# sdvx-controller-hardware.net
KiCad netlist of a schematic drawn in EAGLE
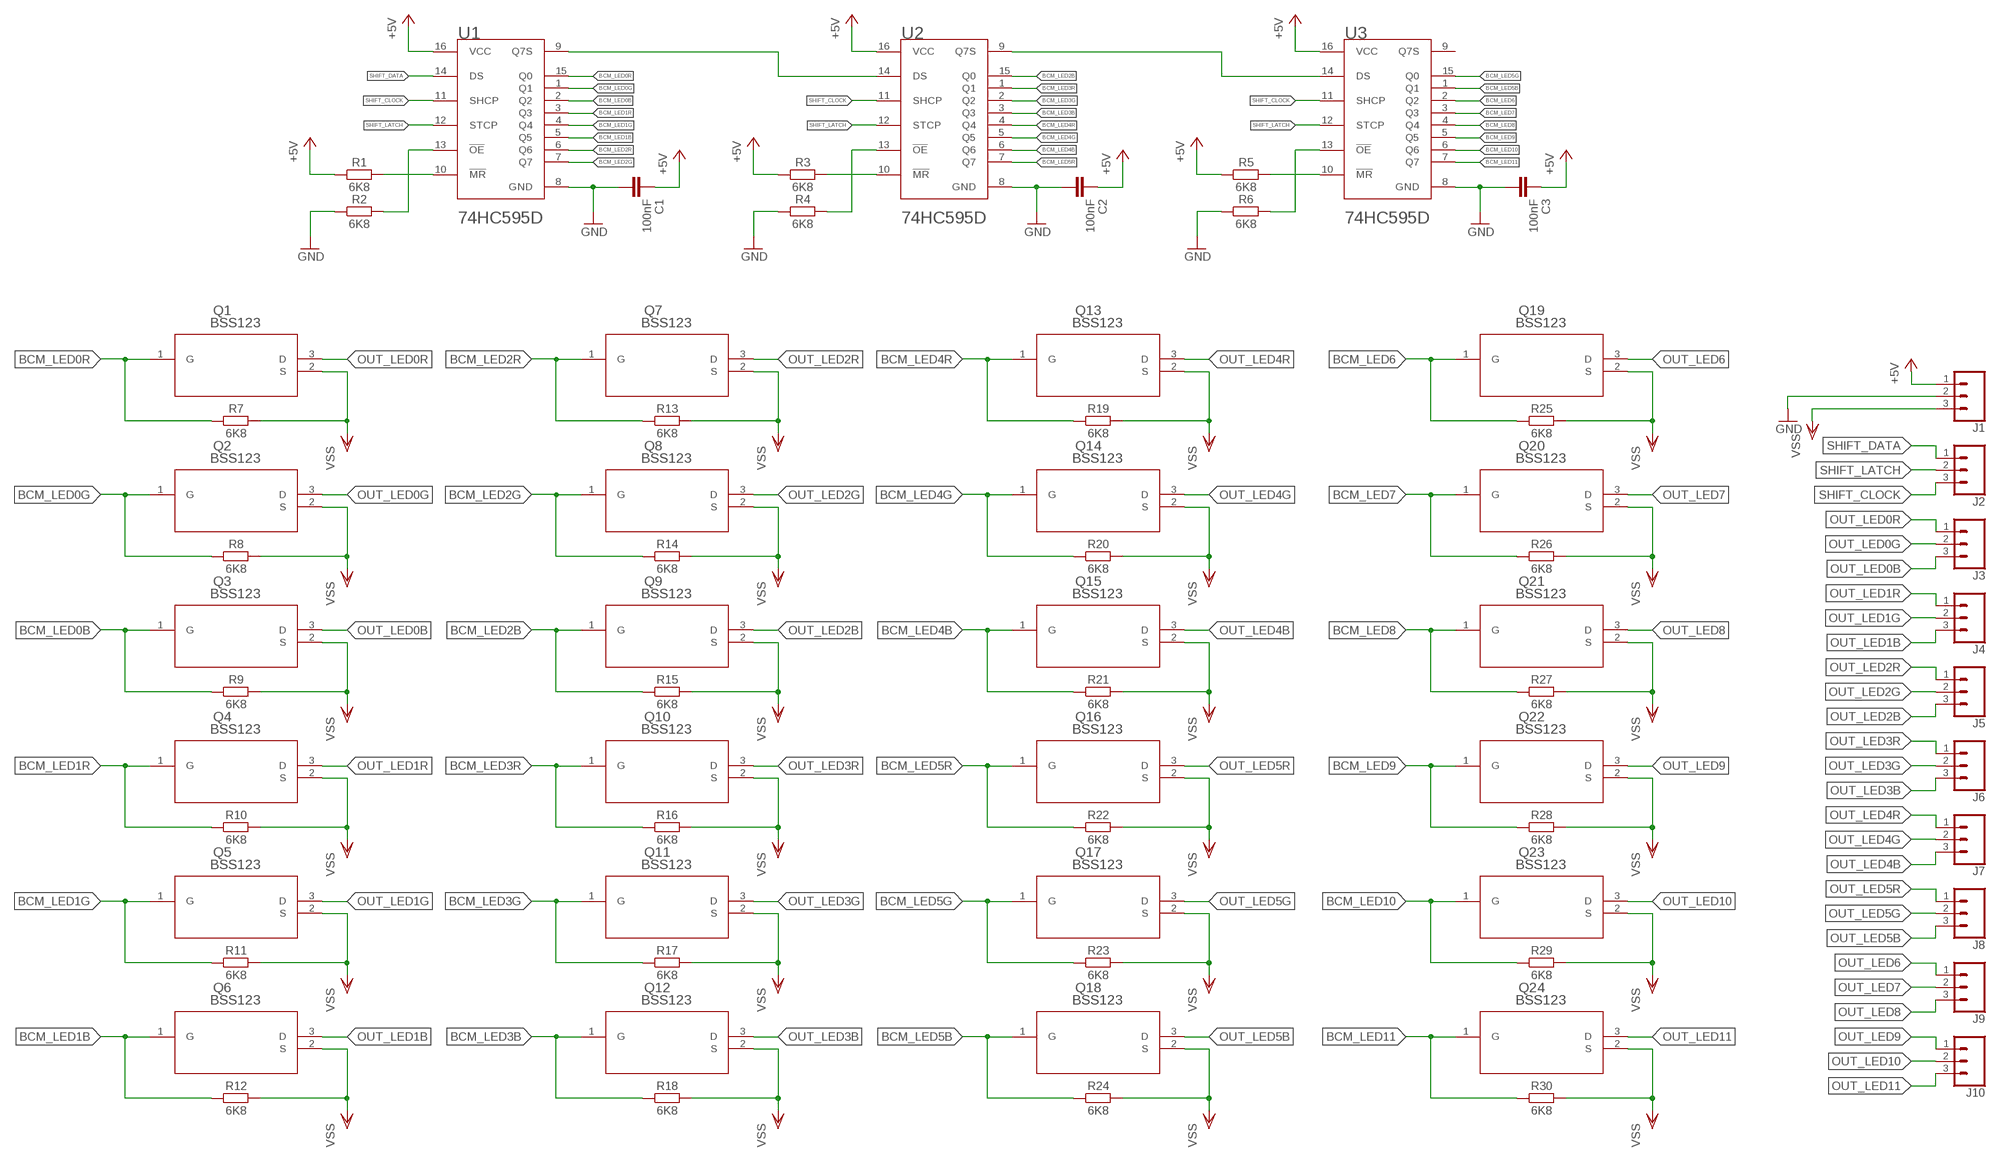
[diagram p0: schematic, sheet 1]

(export (version "E")
  (design (tool "Eeschema 10.0.6"))
  (components
    (comp (ref "C1")
      (value "100nF")
      (footprint "eagle-import:CAPC2012X110")
      (libsource (lib "eagle-import") (part "CCHIP-0805(2012-METRIC)_"))
    )
    (comp (ref "C2")
      (value "100nF")
      (footprint "eagle-import:CAPC2012X110")
      (libsource (lib "eagle-import") (part "CCHIP-0805(2012-METRIC)_"))
    )
    (comp (ref "C3")
      (value "100nF")
      (footprint "eagle-import:CAPC2012X110")
      (libsource (lib "eagle-import") (part "CCHIP-0805(2012-METRIC)_"))
    )
    (comp (ref "J1")
      (value "CONN_03-SCREW-5MM")
      (footprint "eagle-import:SCREWTERMINAL-5MM-3")
      (libsource (lib "eagle-import") (part "CONN_03-SCREW-5MM"))
    )
    (comp (ref "J2")
      (value "CONN_03-SCREW-5MM")
      (footprint "eagle-import:SCREWTERMINAL-5MM-3")
      (libsource (lib "eagle-import") (part "CONN_03-SCREW-5MM"))
    )
    (comp (ref "J3")
      (value "CONN_03-SCREW-5MM")
      (footprint "eagle-import:SCREWTERMINAL-5MM-3")
      (libsource (lib "eagle-import") (part "CONN_03-SCREW-5MM"))
    )
    (comp (ref "J4")
      (value "CONN_03-SCREW-5MM")
      (footprint "eagle-import:SCREWTERMINAL-5MM-3")
      (libsource (lib "eagle-import") (part "CONN_03-SCREW-5MM"))
    )
    (comp (ref "J5")
      (value "CONN_03-SCREW-5MM")
      (footprint "eagle-import:SCREWTERMINAL-5MM-3")
      (libsource (lib "eagle-import") (part "CONN_03-SCREW-5MM"))
    )
    (comp (ref "J6")
      (value "CONN_03-SCREW-5MM")
      (footprint "eagle-import:SCREWTERMINAL-5MM-3")
      (libsource (lib "eagle-import") (part "CONN_03-SCREW-5MM"))
    )
    (comp (ref "J7")
      (value "CONN_03-SCREW-5MM")
      (footprint "eagle-import:SCREWTERMINAL-5MM-3")
      (libsource (lib "eagle-import") (part "CONN_03-SCREW-5MM"))
    )
    (comp (ref "J8")
      (value "CONN_03-SCREW-5MM")
      (footprint "eagle-import:SCREWTERMINAL-5MM-3")
      (libsource (lib "eagle-import") (part "CONN_03-SCREW-5MM"))
    )
    (comp (ref "J9")
      (value "CONN_03-SCREW-5MM")
      (footprint "eagle-import:SCREWTERMINAL-5MM-3")
      (libsource (lib "eagle-import") (part "CONN_03-SCREW-5MM"))
    )
    (comp (ref "J10")
      (value "CONN_03-SCREW-5MM")
      (footprint "eagle-import:SCREWTERMINAL-5MM-3")
      (libsource (lib "eagle-import") (part "CONN_03-SCREW-5MM"))
    )
    (comp (ref "Q1")
      (value "BSS123")
      (footprint "eagle-import:SOT-23-3_1P4X3P040_ONS")
      (fields
        (field (name "MANUFACTURER_PART_NUMBER") "BSS123LT1")
        (field (name "COPYRIGHT") "Copyright (C) 2021 Ultra Librarian. All rights reserved.")
      )
      (libsource (lib "eagle-import") (part "BSS123LT1"))
    )
    (comp (ref "Q2")
      (value "BSS123")
      (footprint "eagle-import:SOT-23-3_1P4X3P040_ONS")
      (fields
        (field (name "MANUFACTURER_PART_NUMBER") "BSS123LT1")
        (field (name "COPYRIGHT") "Copyright (C) 2021 Ultra Librarian. All rights reserved.")
      )
      (libsource (lib "eagle-import") (part "BSS123LT1"))
    )
    (comp (ref "Q3")
      (value "BSS123")
      (footprint "eagle-import:SOT-23-3_1P4X3P040_ONS")
      (fields
        (field (name "MANUFACTURER_PART_NUMBER") "BSS123LT1")
        (field (name "COPYRIGHT") "Copyright (C) 2021 Ultra Librarian. All rights reserved.")
      )
      (libsource (lib "eagle-import") (part "BSS123LT1"))
    )
    (comp (ref "Q4")
      (value "BSS123")
      (footprint "eagle-import:SOT-23-3_1P4X3P040_ONS")
      (fields
        (field (name "MANUFACTURER_PART_NUMBER") "BSS123LT1")
        (field (name "COPYRIGHT") "Copyright (C) 2021 Ultra Librarian. All rights reserved.")
      )
      (libsource (lib "eagle-import") (part "BSS123LT1"))
    )
    (comp (ref "Q5")
      (value "BSS123")
      (footprint "eagle-import:SOT-23-3_1P4X3P040_ONS")
      (fields
        (field (name "MANUFACTURER_PART_NUMBER") "BSS123LT1")
        (field (name "COPYRIGHT") "Copyright (C) 2021 Ultra Librarian. All rights reserved.")
      )
      (libsource (lib "eagle-import") (part "BSS123LT1"))
    )
    (comp (ref "Q6")
      (value "BSS123")
      (footprint "eagle-import:SOT-23-3_1P4X3P040_ONS")
      (fields
        (field (name "MANUFACTURER_PART_NUMBER") "BSS123LT1")
        (field (name "COPYRIGHT") "Copyright (C) 2021 Ultra Librarian. All rights reserved.")
      )
      (libsource (lib "eagle-import") (part "BSS123LT1"))
    )
    (comp (ref "Q7")
      (value "BSS123")
      (footprint "eagle-import:SOT-23-3_1P4X3P040_ONS")
      (fields
        (field (name "MANUFACTURER_PART_NUMBER") "BSS123LT1")
        (field (name "COPYRIGHT") "Copyright (C) 2021 Ultra Librarian. All rights reserved.")
      )
      (libsource (lib "eagle-import") (part "BSS123LT1"))
    )
    (comp (ref "Q8")
      (value "BSS123")
      (footprint "eagle-import:SOT-23-3_1P4X3P040_ONS")
      (fields
        (field (name "MANUFACTURER_PART_NUMBER") "BSS123LT1")
        (field (name "COPYRIGHT") "Copyright (C) 2021 Ultra Librarian. All rights reserved.")
      )
      (libsource (lib "eagle-import") (part "BSS123LT1"))
    )
    (comp (ref "Q9")
      (value "BSS123")
      (footprint "eagle-import:SOT-23-3_1P4X3P040_ONS")
      (fields
        (field (name "MANUFACTURER_PART_NUMBER") "BSS123LT1")
        (field (name "COPYRIGHT") "Copyright (C) 2021 Ultra Librarian. All rights reserved.")
      )
      (libsource (lib "eagle-import") (part "BSS123LT1"))
    )
    (comp (ref "Q10")
      (value "BSS123")
      (footprint "eagle-import:SOT-23-3_1P4X3P040_ONS")
      (fields
        (field (name "MANUFACTURER_PART_NUMBER") "BSS123LT1")
        (field (name "COPYRIGHT") "Copyright (C) 2021 Ultra Librarian. All rights reserved.")
      )
      (libsource (lib "eagle-import") (part "BSS123LT1"))
    )
    (comp (ref "Q11")
      (value "BSS123")
      (footprint "eagle-import:SOT-23-3_1P4X3P040_ONS")
      (fields
        (field (name "MANUFACTURER_PART_NUMBER") "BSS123LT1")
        (field (name "COPYRIGHT") "Copyright (C) 2021 Ultra Librarian. All rights reserved.")
      )
      (libsource (lib "eagle-import") (part "BSS123LT1"))
    )
    (comp (ref "Q12")
      (value "BSS123")
      (footprint "eagle-import:SOT-23-3_1P4X3P040_ONS")
      (fields
        (field (name "MANUFACTURER_PART_NUMBER") "BSS123LT1")
        (field (name "COPYRIGHT") "Copyright (C) 2021 Ultra Librarian. All rights reserved.")
      )
      (libsource (lib "eagle-import") (part "BSS123LT1"))
    )
    (comp (ref "Q13")
      (value "BSS123")
      (footprint "eagle-import:SOT-23-3_1P4X3P040_ONS")
      (fields
        (field (name "MANUFACTURER_PART_NUMBER") "BSS123LT1")
        (field (name "COPYRIGHT") "Copyright (C) 2021 Ultra Librarian. All rights reserved.")
      )
      (libsource (lib "eagle-import") (part "BSS123LT1"))
    )
    (comp (ref "Q14")
      (value "BSS123")
      (footprint "eagle-import:SOT-23-3_1P4X3P040_ONS")
      (fields
        (field (name "MANUFACTURER_PART_NUMBER") "BSS123LT1")
        (field (name "COPYRIGHT") "Copyright (C) 2021 Ultra Librarian. All rights reserved.")
      )
      (libsource (lib "eagle-import") (part "BSS123LT1"))
    )
    (comp (ref "Q15")
      (value "BSS123")
      (footprint "eagle-import:SOT-23-3_1P4X3P040_ONS")
      (fields
        (field (name "MANUFACTURER_PART_NUMBER") "BSS123LT1")
        (field (name "COPYRIGHT") "Copyright (C) 2021 Ultra Librarian. All rights reserved.")
      )
      (libsource (lib "eagle-import") (part "BSS123LT1"))
    )
    (comp (ref "Q16")
      (value "BSS123")
      (footprint "eagle-import:SOT-23-3_1P4X3P040_ONS")
      (fields
        (field (name "MANUFACTURER_PART_NUMBER") "BSS123LT1")
        (field (name "COPYRIGHT") "Copyright (C) 2021 Ultra Librarian. All rights reserved.")
      )
      (libsource (lib "eagle-import") (part "BSS123LT1"))
    )
    (comp (ref "Q17")
      (value "BSS123")
      (footprint "eagle-import:SOT-23-3_1P4X3P040_ONS")
      (fields
        (field (name "MANUFACTURER_PART_NUMBER") "BSS123LT1")
        (field (name "COPYRIGHT") "Copyright (C) 2021 Ultra Librarian. All rights reserved.")
      )
      (libsource (lib "eagle-import") (part "BSS123LT1"))
    )
    (comp (ref "Q18")
      (value "BSS123")
      (footprint "eagle-import:SOT-23-3_1P4X3P040_ONS")
      (fields
        (field (name "MANUFACTURER_PART_NUMBER") "BSS123LT1")
        (field (name "COPYRIGHT") "Copyright (C) 2021 Ultra Librarian. All rights reserved.")
      )
      (libsource (lib "eagle-import") (part "BSS123LT1"))
    )
    (comp (ref "Q19")
      (value "BSS123")
      (footprint "eagle-import:SOT-23-3_1P4X3P040_ONS")
      (fields
        (field (name "MANUFACTURER_PART_NUMBER") "BSS123LT1")
        (field (name "COPYRIGHT") "Copyright (C) 2021 Ultra Librarian. All rights reserved.")
      )
      (libsource (lib "eagle-import") (part "BSS123LT1"))
    )
    (comp (ref "Q20")
      (value "BSS123")
      (footprint "eagle-import:SOT-23-3_1P4X3P040_ONS")
      (fields
        (field (name "MANUFACTURER_PART_NUMBER") "BSS123LT1")
        (field (name "COPYRIGHT") "Copyright (C) 2021 Ultra Librarian. All rights reserved.")
      )
      (libsource (lib "eagle-import") (part "BSS123LT1"))
    )
    (comp (ref "Q21")
      (value "BSS123")
      (footprint "eagle-import:SOT-23-3_1P4X3P040_ONS")
      (fields
        (field (name "MANUFACTURER_PART_NUMBER") "BSS123LT1")
        (field (name "COPYRIGHT") "Copyright (C) 2021 Ultra Librarian. All rights reserved.")
      )
      (libsource (lib "eagle-import") (part "BSS123LT1"))
    )
    (comp (ref "Q22")
      (value "BSS123")
      (footprint "eagle-import:SOT-23-3_1P4X3P040_ONS")
      (fields
        (field (name "MANUFACTURER_PART_NUMBER") "BSS123LT1")
        (field (name "COPYRIGHT") "Copyright (C) 2021 Ultra Librarian. All rights reserved.")
      )
      (libsource (lib "eagle-import") (part "BSS123LT1"))
    )
    (comp (ref "Q23")
      (value "BSS123")
      (footprint "eagle-import:SOT-23-3_1P4X3P040_ONS")
      (fields
        (field (name "MANUFACTURER_PART_NUMBER") "BSS123LT1")
        (field (name "COPYRIGHT") "Copyright (C) 2021 Ultra Librarian. All rights reserved.")
      )
      (libsource (lib "eagle-import") (part "BSS123LT1"))
    )
    (comp (ref "Q24")
      (value "BSS123")
      (footprint "eagle-import:SOT-23-3_1P4X3P040_ONS")
      (fields
        (field (name "MANUFACTURER_PART_NUMBER") "BSS123LT1")
        (field (name "COPYRIGHT") "Copyright (C) 2021 Ultra Librarian. All rights reserved.")
      )
      (libsource (lib "eagle-import") (part "BSS123LT1"))
    )
    (comp (ref "R1")
      (value "6K8")
      (footprint "eagle-import:RESC2012X65")
      (libsource (lib "eagle-import") (part "RCHIP-0805(2012-METRIC)_"))
    )
    (comp (ref "R2")
      (value "6K8")
      (footprint "eagle-import:RESC2012X65")
      (libsource (lib "eagle-import") (part "RCHIP-0805(2012-METRIC)_"))
    )
    (comp (ref "R3")
      (value "6K8")
      (footprint "eagle-import:RESC2012X65")
      (libsource (lib "eagle-import") (part "RCHIP-0805(2012-METRIC)_"))
    )
    (comp (ref "R4")
      (value "6K8")
      (footprint "eagle-import:RESC2012X65")
      (libsource (lib "eagle-import") (part "RCHIP-0805(2012-METRIC)_"))
    )
    (comp (ref "R5")
      (value "6K8")
      (footprint "eagle-import:RESC2012X65")
      (libsource (lib "eagle-import") (part "RCHIP-0805(2012-METRIC)_"))
    )
    (comp (ref "R6")
      (value "6K8")
      (footprint "eagle-import:RESC2012X65")
      (libsource (lib "eagle-import") (part "RCHIP-0805(2012-METRIC)_"))
    )
    (comp (ref "R7")
      (value "6K8")
      (footprint "eagle-import:RESC2012X65")
      (libsource (lib "eagle-import") (part "RCHIP-0805(2012-METRIC)_"))
    )
    (comp (ref "R8")
      (value "6K8")
      (footprint "eagle-import:RESC2012X65")
      (libsource (lib "eagle-import") (part "RCHIP-0805(2012-METRIC)_"))
    )
    (comp (ref "R9")
      (value "6K8")
      (footprint "eagle-import:RESC2012X65")
      (libsource (lib "eagle-import") (part "RCHIP-0805(2012-METRIC)_"))
    )
    (comp (ref "R10")
      (value "6K8")
      (footprint "eagle-import:RESC2012X65")
      (libsource (lib "eagle-import") (part "RCHIP-0805(2012-METRIC)_"))
    )
    (comp (ref "R11")
      (value "6K8")
      (footprint "eagle-import:RESC2012X65")
      (libsource (lib "eagle-import") (part "RCHIP-0805(2012-METRIC)_"))
    )
    (comp (ref "R12")
      (value "6K8")
      (footprint "eagle-import:RESC2012X65")
      (libsource (lib "eagle-import") (part "RCHIP-0805(2012-METRIC)_"))
    )
    (comp (ref "R13")
      (value "6K8")
      (footprint "eagle-import:RESC2012X65")
      (libsource (lib "eagle-import") (part "RCHIP-0805(2012-METRIC)_"))
    )
    (comp (ref "R14")
      (value "6K8")
      (footprint "eagle-import:RESC2012X65")
      (libsource (lib "eagle-import") (part "RCHIP-0805(2012-METRIC)_"))
    )
    (comp (ref "R15")
      (value "6K8")
      (footprint "eagle-import:RESC2012X65")
      (libsource (lib "eagle-import") (part "RCHIP-0805(2012-METRIC)_"))
    )
    (comp (ref "R16")
      (value "6K8")
      (footprint "eagle-import:RESC2012X65")
      (libsource (lib "eagle-import") (part "RCHIP-0805(2012-METRIC)_"))
    )
    (comp (ref "R17")
      (value "6K8")
      (footprint "eagle-import:RESC2012X65")
      (libsource (lib "eagle-import") (part "RCHIP-0805(2012-METRIC)_"))
    )
    (comp (ref "R18")
      (value "6K8")
      (footprint "eagle-import:RESC2012X65")
      (libsource (lib "eagle-import") (part "RCHIP-0805(2012-METRIC)_"))
    )
    (comp (ref "R19")
      (value "6K8")
      (footprint "eagle-import:RESC2012X65")
      (libsource (lib "eagle-import") (part "RCHIP-0805(2012-METRIC)_"))
    )
    (comp (ref "R20")
      (value "6K8")
      (footprint "eagle-import:RESC2012X65")
      (libsource (lib "eagle-import") (part "RCHIP-0805(2012-METRIC)_"))
    )
    (comp (ref "R21")
      (value "6K8")
      (footprint "eagle-import:RESC2012X65")
      (libsource (lib "eagle-import") (part "RCHIP-0805(2012-METRIC)_"))
    )
    (comp (ref "R22")
      (value "6K8")
      (footprint "eagle-import:RESC2012X65")
      (libsource (lib "eagle-import") (part "RCHIP-0805(2012-METRIC)_"))
    )
    (comp (ref "R23")
      (value "6K8")
      (footprint "eagle-import:RESC2012X65")
      (libsource (lib "eagle-import") (part "RCHIP-0805(2012-METRIC)_"))
    )
    (comp (ref "R24")
      (value "6K8")
      (footprint "eagle-import:RESC2012X65")
      (libsource (lib "eagle-import") (part "RCHIP-0805(2012-METRIC)_"))
    )
    (comp (ref "R25")
      (value "6K8")
      (footprint "eagle-import:RESC2012X65")
      (libsource (lib "eagle-import") (part "RCHIP-0805(2012-METRIC)_"))
    )
    (comp (ref "R26")
      (value "6K8")
      (footprint "eagle-import:RESC2012X65")
      (libsource (lib "eagle-import") (part "RCHIP-0805(2012-METRIC)_"))
    )
    (comp (ref "R27")
      (value "6K8")
      (footprint "eagle-import:RESC2012X65")
      (libsource (lib "eagle-import") (part "RCHIP-0805(2012-METRIC)_"))
    )
    (comp (ref "R28")
      (value "6K8")
      (footprint "eagle-import:RESC2012X65")
      (libsource (lib "eagle-import") (part "RCHIP-0805(2012-METRIC)_"))
    )
    (comp (ref "R29")
      (value "6K8")
      (footprint "eagle-import:RESC2012X65")
      (libsource (lib "eagle-import") (part "RCHIP-0805(2012-METRIC)_"))
    )
    (comp (ref "R30")
      (value "6K8")
      (footprint "eagle-import:RESC2012X65")
      (libsource (lib "eagle-import") (part "RCHIP-0805(2012-METRIC)_"))
    )
    (comp (ref "U1")
      (value "NEXPERIA_74HC595DNEXPERIA_74HC595D_0_0")
      (footprint "eagle-import:NEXPERIA_74HC595D_0")
      (fields
        (field (name "DIGIKEY_PART_NUMBER") "1727-2821-1-ND")
        (field (name "MF") "Nexperia")
        (field (name "MOUSER_PART_NUMBER") "771-74HC595D-T")
      )
      (libsource (lib "eagle-import") (part "NEXPERIA_74HC595DNEXPERIA_74HC595D_0_0"))
    )
    (comp (ref "U2")
      (value "NEXPERIA_74HC595DNEXPERIA_74HC595D_0_0")
      (footprint "eagle-import:NEXPERIA_74HC595D_0")
      (fields
        (field (name "DIGIKEY_PART_NUMBER") "1727-2821-1-ND")
        (field (name "MF") "Nexperia")
        (field (name "MOUSER_PART_NUMBER") "771-74HC595D-T")
      )
      (libsource (lib "eagle-import") (part "NEXPERIA_74HC595DNEXPERIA_74HC595D_0_0"))
    )
    (comp (ref "U3")
      (value "NEXPERIA_74HC595DNEXPERIA_74HC595D_0_0")
      (footprint "eagle-import:NEXPERIA_74HC595D_0")
      (fields
        (field (name "DIGIKEY_PART_NUMBER") "1727-2821-1-ND")
        (field (name "MF") "Nexperia")
        (field (name "MOUSER_PART_NUMBER") "771-74HC595D-T")
      )
      (libsource (lib "eagle-import") (part "NEXPERIA_74HC595DNEXPERIA_74HC595D_0_0"))
    )
  )
  (nets
    (net (code "1") (name "+5V") (class "Default")
      (node (ref "C1") (pin "1") (pinfunction "1_1") (pintype "passive"))
      (node (ref "C2") (pin "1") (pinfunction "1_1") (pintype "passive"))
      (node (ref "C3") (pin "1") (pinfunction "1_1") (pintype "passive"))
      (node (ref "J1") (pin "1") (pinfunction "1_1") (pintype "passive"))
      (node (ref "R1") (pin "1") (pinfunction "1_1") (pintype "passive"))
      (node (ref "R3") (pin "1") (pinfunction "1_1") (pintype "passive"))
      (node (ref "R5") (pin "1") (pinfunction "1_1") (pintype "passive"))
      (node (ref "U1") (pin "16") (pinfunction "VCC_16") (pintype "power_in"))
      (node (ref "U2") (pin "16") (pinfunction "VCC_16") (pintype "power_in"))
      (node (ref "U3") (pin "16") (pinfunction "VCC_16") (pintype "power_in"))
    )
    (net (code "2") (name "BCM_LED0B") (class "Default")
      (node (ref "Q3") (pin "1") (pinfunction "G_1") (pintype "passive"))
      (node (ref "R9") (pin "1") (pinfunction "1_1") (pintype "passive"))
      (node (ref "U1") (pin "2") (pinfunction "Q2_2") (pintype "output"))
    )
    (net (code "3") (name "BCM_LED0G") (class "Default")
      (node (ref "Q2") (pin "1") (pinfunction "G_1") (pintype "passive"))
      (node (ref "R8") (pin "1") (pinfunction "1_1") (pintype "passive"))
      (node (ref "U1") (pin "1") (pinfunction "Q1_1") (pintype "output"))
    )
    (net (code "4") (name "BCM_LED0R") (class "Default")
      (node (ref "Q1") (pin "1") (pinfunction "G_1") (pintype "passive"))
      (node (ref "R7") (pin "1") (pinfunction "1_1") (pintype "passive"))
      (node (ref "U1") (pin "15") (pinfunction "Q0_15") (pintype "output"))
    )
    (net (code "5") (name "BCM_LED1B") (class "Default")
      (node (ref "Q6") (pin "1") (pinfunction "G_1") (pintype "passive"))
      (node (ref "R12") (pin "1") (pinfunction "1_1") (pintype "passive"))
      (node (ref "U1") (pin "5") (pinfunction "Q5_5") (pintype "output"))
    )
    (net (code "6") (name "BCM_LED1G") (class "Default")
      (node (ref "Q5") (pin "1") (pinfunction "G_1") (pintype "passive"))
      (node (ref "R11") (pin "1") (pinfunction "1_1") (pintype "passive"))
      (node (ref "U1") (pin "4") (pinfunction "Q4_4") (pintype "output"))
    )
    (net (code "7") (name "BCM_LED1R") (class "Default")
      (node (ref "Q4") (pin "1") (pinfunction "G_1") (pintype "passive"))
      (node (ref "R10") (pin "1") (pinfunction "1_1") (pintype "passive"))
      (node (ref "U1") (pin "3") (pinfunction "Q3_3") (pintype "output"))
    )
    (net (code "8") (name "BCM_LED2B") (class "Default")
      (node (ref "Q9") (pin "1") (pinfunction "G_1") (pintype "passive"))
      (node (ref "R15") (pin "1") (pinfunction "1_1") (pintype "passive"))
      (node (ref "U2") (pin "15") (pinfunction "Q0_15") (pintype "output"))
    )
    (net (code "9") (name "BCM_LED2G") (class "Default")
      (node (ref "Q8") (pin "1") (pinfunction "G_1") (pintype "passive"))
      (node (ref "R14") (pin "1") (pinfunction "1_1") (pintype "passive"))
      (node (ref "U1") (pin "7") (pinfunction "Q7_7") (pintype "output"))
    )
    (net (code "10") (name "BCM_LED2R") (class "Default")
      (node (ref "Q7") (pin "1") (pinfunction "G_1") (pintype "passive"))
      (node (ref "R13") (pin "1") (pinfunction "1_1") (pintype "passive"))
      (node (ref "U1") (pin "6") (pinfunction "Q6_6") (pintype "output"))
    )
    (net (code "11") (name "BCM_LED3B") (class "Default")
      (node (ref "Q12") (pin "1") (pinfunction "G_1") (pintype "passive"))
      (node (ref "R18") (pin "1") (pinfunction "1_1") (pintype "passive"))
      (node (ref "U2") (pin "3") (pinfunction "Q3_3") (pintype "output"))
    )
    (net (code "12") (name "BCM_LED3G") (class "Default")
      (node (ref "Q11") (pin "1") (pinfunction "G_1") (pintype "passive"))
      (node (ref "R17") (pin "1") (pinfunction "1_1") (pintype "passive"))
      (node (ref "U2") (pin "2") (pinfunction "Q2_2") (pintype "output"))
    )
    (net (code "13") (name "BCM_LED3R") (class "Default")
      (node (ref "Q10") (pin "1") (pinfunction "G_1") (pintype "passive"))
      (node (ref "R16") (pin "1") (pinfunction "1_1") (pintype "passive"))
      (node (ref "U2") (pin "1") (pinfunction "Q1_1") (pintype "output"))
    )
    (net (code "14") (name "BCM_LED4B") (class "Default")
      (node (ref "Q15") (pin "1") (pinfunction "G_1") (pintype "passive"))
      (node (ref "R21") (pin "1") (pinfunction "1_1") (pintype "passive"))
      (node (ref "U2") (pin "6") (pinfunction "Q6_6") (pintype "output"))
    )
    (net (code "15") (name "BCM_LED4G") (class "Default")
      (node (ref "Q14") (pin "1") (pinfunction "G_1") (pintype "passive"))
      (node (ref "R20") (pin "1") (pinfunction "1_1") (pintype "passive"))
      (node (ref "U2") (pin "5") (pinfunction "Q5_5") (pintype "output"))
    )
    (net (code "16") (name "BCM_LED4R") (class "Default")
      (node (ref "Q13") (pin "1") (pinfunction "G_1") (pintype "passive"))
      (node (ref "R19") (pin "1") (pinfunction "1_1") (pintype "passive"))
      (node (ref "U2") (pin "4") (pinfunction "Q4_4") (pintype "output"))
    )
    (net (code "17") (name "BCM_LED5B") (class "Default")
      (node (ref "Q18") (pin "1") (pinfunction "G_1") (pintype "passive"))
      (node (ref "R24") (pin "1") (pinfunction "1_1") (pintype "passive"))
      (node (ref "U3") (pin "1") (pinfunction "Q1_1") (pintype "output"))
    )
    (net (code "18") (name "BCM_LED5G") (class "Default")
      (node (ref "Q17") (pin "1") (pinfunction "G_1") (pintype "passive"))
      (node (ref "R23") (pin "1") (pinfunction "1_1") (pintype "passive"))
      (node (ref "U3") (pin "15") (pinfunction "Q0_15") (pintype "output"))
    )
    (net (code "19") (name "BCM_LED5R") (class "Default")
      (node (ref "Q16") (pin "1") (pinfunction "G_1") (pintype "passive"))
      (node (ref "R22") (pin "1") (pinfunction "1_1") (pintype "passive"))
      (node (ref "U2") (pin "7") (pinfunction "Q7_7") (pintype "output"))
    )
    (net (code "20") (name "BCM_LED6") (class "Default")
      (node (ref "Q19") (pin "1") (pinfunction "G_1") (pintype "passive"))
      (node (ref "R25") (pin "1") (pinfunction "1_1") (pintype "passive"))
      (node (ref "U3") (pin "2") (pinfunction "Q2_2") (pintype "output"))
    )
    (net (code "21") (name "BCM_LED7") (class "Default")
      (node (ref "Q20") (pin "1") (pinfunction "G_1") (pintype "passive"))
      (node (ref "R26") (pin "1") (pinfunction "1_1") (pintype "passive"))
      (node (ref "U3") (pin "3") (pinfunction "Q3_3") (pintype "output"))
    )
    (net (code "22") (name "BCM_LED8") (class "Default")
      (node (ref "Q21") (pin "1") (pinfunction "G_1") (pintype "passive"))
      (node (ref "R27") (pin "1") (pinfunction "1_1") (pintype "passive"))
      (node (ref "U3") (pin "4") (pinfunction "Q4_4") (pintype "output"))
    )
    (net (code "23") (name "BCM_LED9") (class "Default")
      (node (ref "Q22") (pin "1") (pinfunction "G_1") (pintype "passive"))
      (node (ref "R28") (pin "1") (pinfunction "1_1") (pintype "passive"))
      (node (ref "U3") (pin "5") (pinfunction "Q5_5") (pintype "output"))
    )
    (net (code "24") (name "BCM_LED10") (class "Default")
      (node (ref "Q23") (pin "1") (pinfunction "G_1") (pintype "passive"))
      (node (ref "R29") (pin "1") (pinfunction "1_1") (pintype "passive"))
      (node (ref "U3") (pin "6") (pinfunction "Q6_6") (pintype "output"))
    )
    (net (code "25") (name "BCM_LED11") (class "Default")
      (node (ref "Q24") (pin "1") (pinfunction "G_1") (pintype "passive"))
      (node (ref "R30") (pin "1") (pinfunction "1_1") (pintype "passive"))
      (node (ref "U3") (pin "7") (pinfunction "Q7_7") (pintype "output"))
    )
    (net (code "26") (name "GND") (class "Default")
      (node (ref "C1") (pin "2") (pinfunction "2_2") (pintype "passive"))
      (node (ref "C2") (pin "2") (pinfunction "2_2") (pintype "passive"))
      (node (ref "C3") (pin "2") (pinfunction "2_2") (pintype "passive"))
      (node (ref "J1") (pin "2") (pinfunction "2_2") (pintype "passive"))
      (node (ref "R2") (pin "1") (pinfunction "1_1") (pintype "passive"))
      (node (ref "R4") (pin "1") (pinfunction "1_1") (pintype "passive"))
      (node (ref "R6") (pin "1") (pinfunction "1_1") (pintype "passive"))
      (node (ref "U1") (pin "8") (pinfunction "GND_8") (pintype "power_in"))
      (node (ref "U2") (pin "8") (pinfunction "GND_8") (pintype "power_in"))
      (node (ref "U3") (pin "8") (pinfunction "GND_8") (pintype "power_in"))
    )
    (net (code "27") (name "Net-(U1-Q7S)") (class "Default")
      (node (ref "U1") (pin "9") (pinfunction "Q7S_9") (pintype "output"))
      (node (ref "U2") (pin "14") (pinfunction "DS_14") (pintype "input"))
    )
    (net (code "28") (name "Net-(U1-~{MR})") (class "Default")
      (node (ref "R1") (pin "2") (pinfunction "2_2") (pintype "passive"))
      (node (ref "U1") (pin "10") (pinfunction "~{MR}_10") (pintype "input"))
    )
    (net (code "29") (name "Net-(U1-~{OE})") (class "Default")
      (node (ref "R2") (pin "2") (pinfunction "2_2") (pintype "passive"))
      (node (ref "U1") (pin "13") (pinfunction "~{OE}_13") (pintype "input"))
    )
    (net (code "30") (name "Net-(U2-Q7S)") (class "Default")
      (node (ref "U2") (pin "9") (pinfunction "Q7S_9") (pintype "output"))
      (node (ref "U3") (pin "14") (pinfunction "DS_14") (pintype "input"))
    )
    (net (code "31") (name "Net-(U2-~{MR})") (class "Default")
      (node (ref "R3") (pin "2") (pinfunction "2_2") (pintype "passive"))
      (node (ref "U2") (pin "10") (pinfunction "~{MR}_10") (pintype "input"))
    )
    (net (code "32") (name "Net-(U2-~{OE})") (class "Default")
      (node (ref "R4") (pin "2") (pinfunction "2_2") (pintype "passive"))
      (node (ref "U2") (pin "13") (pinfunction "~{OE}_13") (pintype "input"))
    )
    (net (code "33") (name "Net-(U3-~{MR})") (class "Default")
      (node (ref "R5") (pin "2") (pinfunction "2_2") (pintype "passive"))
      (node (ref "U3") (pin "10") (pinfunction "~{MR}_10") (pintype "input"))
    )
    (net (code "34") (name "Net-(U3-~{OE})") (class "Default")
      (node (ref "R6") (pin "2") (pinfunction "2_2") (pintype "passive"))
      (node (ref "U3") (pin "13") (pinfunction "~{OE}_13") (pintype "input"))
    )
    (net (code "35") (name "OUT_LED0B") (class "Default")
      (node (ref "J3") (pin "3") (pinfunction "3_3") (pintype "passive"))
      (node (ref "Q3") (pin "3") (pinfunction "D_3") (pintype "passive"))
    )
    (net (code "36") (name "OUT_LED0G") (class "Default")
      (node (ref "J3") (pin "2") (pinfunction "2_2") (pintype "passive"))
      (node (ref "Q2") (pin "3") (pinfunction "D_3") (pintype "passive"))
    )
    (net (code "37") (name "OUT_LED0R") (class "Default")
      (node (ref "J3") (pin "1") (pinfunction "1_1") (pintype "passive"))
      (node (ref "Q1") (pin "3") (pinfunction "D_3") (pintype "passive"))
    )
    (net (code "38") (name "OUT_LED1B") (class "Default")
      (node (ref "J4") (pin "3") (pinfunction "3_3") (pintype "passive"))
      (node (ref "Q6") (pin "3") (pinfunction "D_3") (pintype "passive"))
    )
    (net (code "39") (name "OUT_LED1G") (class "Default")
      (node (ref "J4") (pin "2") (pinfunction "2_2") (pintype "passive"))
      (node (ref "Q5") (pin "3") (pinfunction "D_3") (pintype "passive"))
    )
    (net (code "40") (name "OUT_LED1R") (class "Default")
      (node (ref "J4") (pin "1") (pinfunction "1_1") (pintype "passive"))
      (node (ref "Q4") (pin "3") (pinfunction "D_3") (pintype "passive"))
    )
    (net (code "41") (name "OUT_LED2B") (class "Default")
      (node (ref "J5") (pin "3") (pinfunction "3_3") (pintype "passive"))
      (node (ref "Q9") (pin "3") (pinfunction "D_3") (pintype "passive"))
    )
    (net (code "42") (name "OUT_LED2G") (class "Default")
      (node (ref "J5") (pin "2") (pinfunction "2_2") (pintype "passive"))
      (node (ref "Q8") (pin "3") (pinfunction "D_3") (pintype "passive"))
    )
    (net (code "43") (name "OUT_LED2R") (class "Default")
      (node (ref "J5") (pin "1") (pinfunction "1_1") (pintype "passive"))
      (node (ref "Q7") (pin "3") (pinfunction "D_3") (pintype "passive"))
    )
    (net (code "44") (name "OUT_LED3B") (class "Default")
      (node (ref "J6") (pin "3") (pinfunction "3_3") (pintype "passive"))
      (node (ref "Q12") (pin "3") (pinfunction "D_3") (pintype "passive"))
    )
    (net (code "45") (name "OUT_LED3G") (class "Default")
      (node (ref "J6") (pin "2") (pinfunction "2_2") (pintype "passive"))
      (node (ref "Q11") (pin "3") (pinfunction "D_3") (pintype "passive"))
    )
    (net (code "46") (name "OUT_LED3R") (class "Default")
      (node (ref "J6") (pin "1") (pinfunction "1_1") (pintype "passive"))
      (node (ref "Q10") (pin "3") (pinfunction "D_3") (pintype "passive"))
    )
    (net (code "47") (name "OUT_LED4B") (class "Default")
      (node (ref "J7") (pin "3") (pinfunction "3_3") (pintype "passive"))
      (node (ref "Q15") (pin "3") (pinfunction "D_3") (pintype "passive"))
    )
    (net (code "48") (name "OUT_LED4G") (class "Default")
      (node (ref "J7") (pin "2") (pinfunction "2_2") (pintype "passive"))
      (node (ref "Q14") (pin "3") (pinfunction "D_3") (pintype "passive"))
    )
    (net (code "49") (name "OUT_LED4R") (class "Default")
      (node (ref "J7") (pin "1") (pinfunction "1_1") (pintype "passive"))
      (node (ref "Q13") (pin "3") (pinfunction "D_3") (pintype "passive"))
    )
    (net (code "50") (name "OUT_LED5B") (class "Default")
      (node (ref "J8") (pin "3") (pinfunction "3_3") (pintype "passive"))
      (node (ref "Q18") (pin "3") (pinfunction "D_3") (pintype "passive"))
    )
    (net (code "51") (name "OUT_LED5G") (class "Default")
      (node (ref "J8") (pin "2") (pinfunction "2_2") (pintype "passive"))
      (node (ref "Q17") (pin "3") (pinfunction "D_3") (pintype "passive"))
    )
    (net (code "52") (name "OUT_LED5R") (class "Default")
      (node (ref "J8") (pin "1") (pinfunction "1_1") (pintype "passive"))
      (node (ref "Q16") (pin "3") (pinfunction "D_3") (pintype "passive"))
    )
    (net (code "53") (name "OUT_LED6") (class "Default")
      (node (ref "J9") (pin "1") (pinfunction "1_1") (pintype "passive"))
      (node (ref "Q19") (pin "3") (pinfunction "D_3") (pintype "passive"))
    )
    (net (code "54") (name "OUT_LED7") (class "Default")
      (node (ref "J9") (pin "2") (pinfunction "2_2") (pintype "passive"))
      (node (ref "Q20") (pin "3") (pinfunction "D_3") (pintype "passive"))
    )
    (net (code "55") (name "OUT_LED8") (class "Default")
      (node (ref "J9") (pin "3") (pinfunction "3_3") (pintype "passive"))
      (node (ref "Q21") (pin "3") (pinfunction "D_3") (pintype "passive"))
    )
    (net (code "56") (name "OUT_LED9") (class "Default")
      (node (ref "J10") (pin "1") (pinfunction "1_1") (pintype "passive"))
      (node (ref "Q22") (pin "3") (pinfunction "D_3") (pintype "passive"))
    )
    (net (code "57") (name "OUT_LED10") (class "Default")
      (node (ref "J10") (pin "2") (pinfunction "2_2") (pintype "passive"))
      (node (ref "Q23") (pin "3") (pinfunction "D_3") (pintype "passive"))
    )
    (net (code "58") (name "OUT_LED11") (class "Default")
      (node (ref "J10") (pin "3") (pinfunction "3_3") (pintype "passive"))
      (node (ref "Q24") (pin "3") (pinfunction "D_3") (pintype "passive"))
    )
    (net (code "59") (name "SHIFT_CLOCK") (class "Default")
      (node (ref "J2") (pin "3") (pinfunction "3_3") (pintype "passive"))
      (node (ref "U1") (pin "11") (pinfunction "SHCP_11") (pintype "input"))
      (node (ref "U2") (pin "11") (pinfunction "SHCP_11") (pintype "input"))
      (node (ref "U3") (pin "11") (pinfunction "SHCP_11") (pintype "input"))
    )
    (net (code "60") (name "SHIFT_DATA") (class "Default")
      (node (ref "J2") (pin "1") (pinfunction "1_1") (pintype "passive"))
      (node (ref "U1") (pin "14") (pinfunction "DS_14") (pintype "input"))
    )
    (net (code "61") (name "SHIFT_LATCH") (class "Default")
      (node (ref "J2") (pin "2") (pinfunction "2_2") (pintype "passive"))
      (node (ref "U1") (pin "12") (pinfunction "STCP_12") (pintype "input"))
      (node (ref "U2") (pin "12") (pinfunction "STCP_12") (pintype "input"))
      (node (ref "U3") (pin "12") (pinfunction "STCP_12") (pintype "input"))
    )
    (net (code "62") (name "VSS") (class "Default")
      (node (ref "J1") (pin "3") (pinfunction "3_3") (pintype "passive"))
      (node (ref "Q1") (pin "2") (pinfunction "S_2") (pintype "passive"))
      (node (ref "Q10") (pin "2") (pinfunction "S_2") (pintype "passive"))
      (node (ref "Q11") (pin "2") (pinfunction "S_2") (pintype "passive"))
      (node (ref "Q12") (pin "2") (pinfunction "S_2") (pintype "passive"))
      (node (ref "Q13") (pin "2") (pinfunction "S_2") (pintype "passive"))
      (node (ref "Q14") (pin "2") (pinfunction "S_2") (pintype "passive"))
      (node (ref "Q15") (pin "2") (pinfunction "S_2") (pintype "passive"))
      (node (ref "Q16") (pin "2") (pinfunction "S_2") (pintype "passive"))
      (node (ref "Q17") (pin "2") (pinfunction "S_2") (pintype "passive"))
      (node (ref "Q18") (pin "2") (pinfunction "S_2") (pintype "passive"))
      (node (ref "Q19") (pin "2") (pinfunction "S_2") (pintype "passive"))
      (node (ref "Q2") (pin "2") (pinfunction "S_2") (pintype "passive"))
      (node (ref "Q20") (pin "2") (pinfunction "S_2") (pintype "passive"))
      (node (ref "Q21") (pin "2") (pinfunction "S_2") (pintype "passive"))
      (node (ref "Q22") (pin "2") (pinfunction "S_2") (pintype "passive"))
      (node (ref "Q23") (pin "2") (pinfunction "S_2") (pintype "passive"))
      (node (ref "Q24") (pin "2") (pinfunction "S_2") (pintype "passive"))
      (node (ref "Q3") (pin "2") (pinfunction "S_2") (pintype "passive"))
      (node (ref "Q4") (pin "2") (pinfunction "S_2") (pintype "passive"))
      (node (ref "Q5") (pin "2") (pinfunction "S_2") (pintype "passive"))
      (node (ref "Q6") (pin "2") (pinfunction "S_2") (pintype "passive"))
      (node (ref "Q7") (pin "2") (pinfunction "S_2") (pintype "passive"))
      (node (ref "Q8") (pin "2") (pinfunction "S_2") (pintype "passive"))
      (node (ref "Q9") (pin "2") (pinfunction "S_2") (pintype "passive"))
      (node (ref "R10") (pin "2") (pinfunction "2_2") (pintype "passive"))
      (node (ref "R11") (pin "2") (pinfunction "2_2") (pintype "passive"))
      (node (ref "R12") (pin "2") (pinfunction "2_2") (pintype "passive"))
      (node (ref "R13") (pin "2") (pinfunction "2_2") (pintype "passive"))
      (node (ref "R14") (pin "2") (pinfunction "2_2") (pintype "passive"))
      (node (ref "R15") (pin "2") (pinfunction "2_2") (pintype "passive"))
      (node (ref "R16") (pin "2") (pinfunction "2_2") (pintype "passive"))
      (node (ref "R17") (pin "2") (pinfunction "2_2") (pintype "passive"))
      (node (ref "R18") (pin "2") (pinfunction "2_2") (pintype "passive"))
      (node (ref "R19") (pin "2") (pinfunction "2_2") (pintype "passive"))
      (node (ref "R20") (pin "2") (pinfunction "2_2") (pintype "passive"))
      (node (ref "R21") (pin "2") (pinfunction "2_2") (pintype "passive"))
      (node (ref "R22") (pin "2") (pinfunction "2_2") (pintype "passive"))
      (node (ref "R23") (pin "2") (pinfunction "2_2") (pintype "passive"))
      (node (ref "R24") (pin "2") (pinfunction "2_2") (pintype "passive"))
      (node (ref "R25") (pin "2") (pinfunction "2_2") (pintype "passive"))
      (node (ref "R26") (pin "2") (pinfunction "2_2") (pintype "passive"))
      (node (ref "R27") (pin "2") (pinfunction "2_2") (pintype "passive"))
      (node (ref "R28") (pin "2") (pinfunction "2_2") (pintype "passive"))
      (node (ref "R29") (pin "2") (pinfunction "2_2") (pintype "passive"))
      (node (ref "R30") (pin "2") (pinfunction "2_2") (pintype "passive"))
      (node (ref "R7") (pin "2") (pinfunction "2_2") (pintype "passive"))
      (node (ref "R8") (pin "2") (pinfunction "2_2") (pintype "passive"))
      (node (ref "R9") (pin "2") (pinfunction "2_2") (pintype "passive"))
    )
    (net (code "63") (name "unconnected-(U3-Q7S-Pad9)") (class "Default")
      (node (ref "U3") (pin "9") (pinfunction "Q7S_9") (pintype "output"))
    )
  )
)
